# working.net
KiCad netlist of a schematic drawn in EAGLE
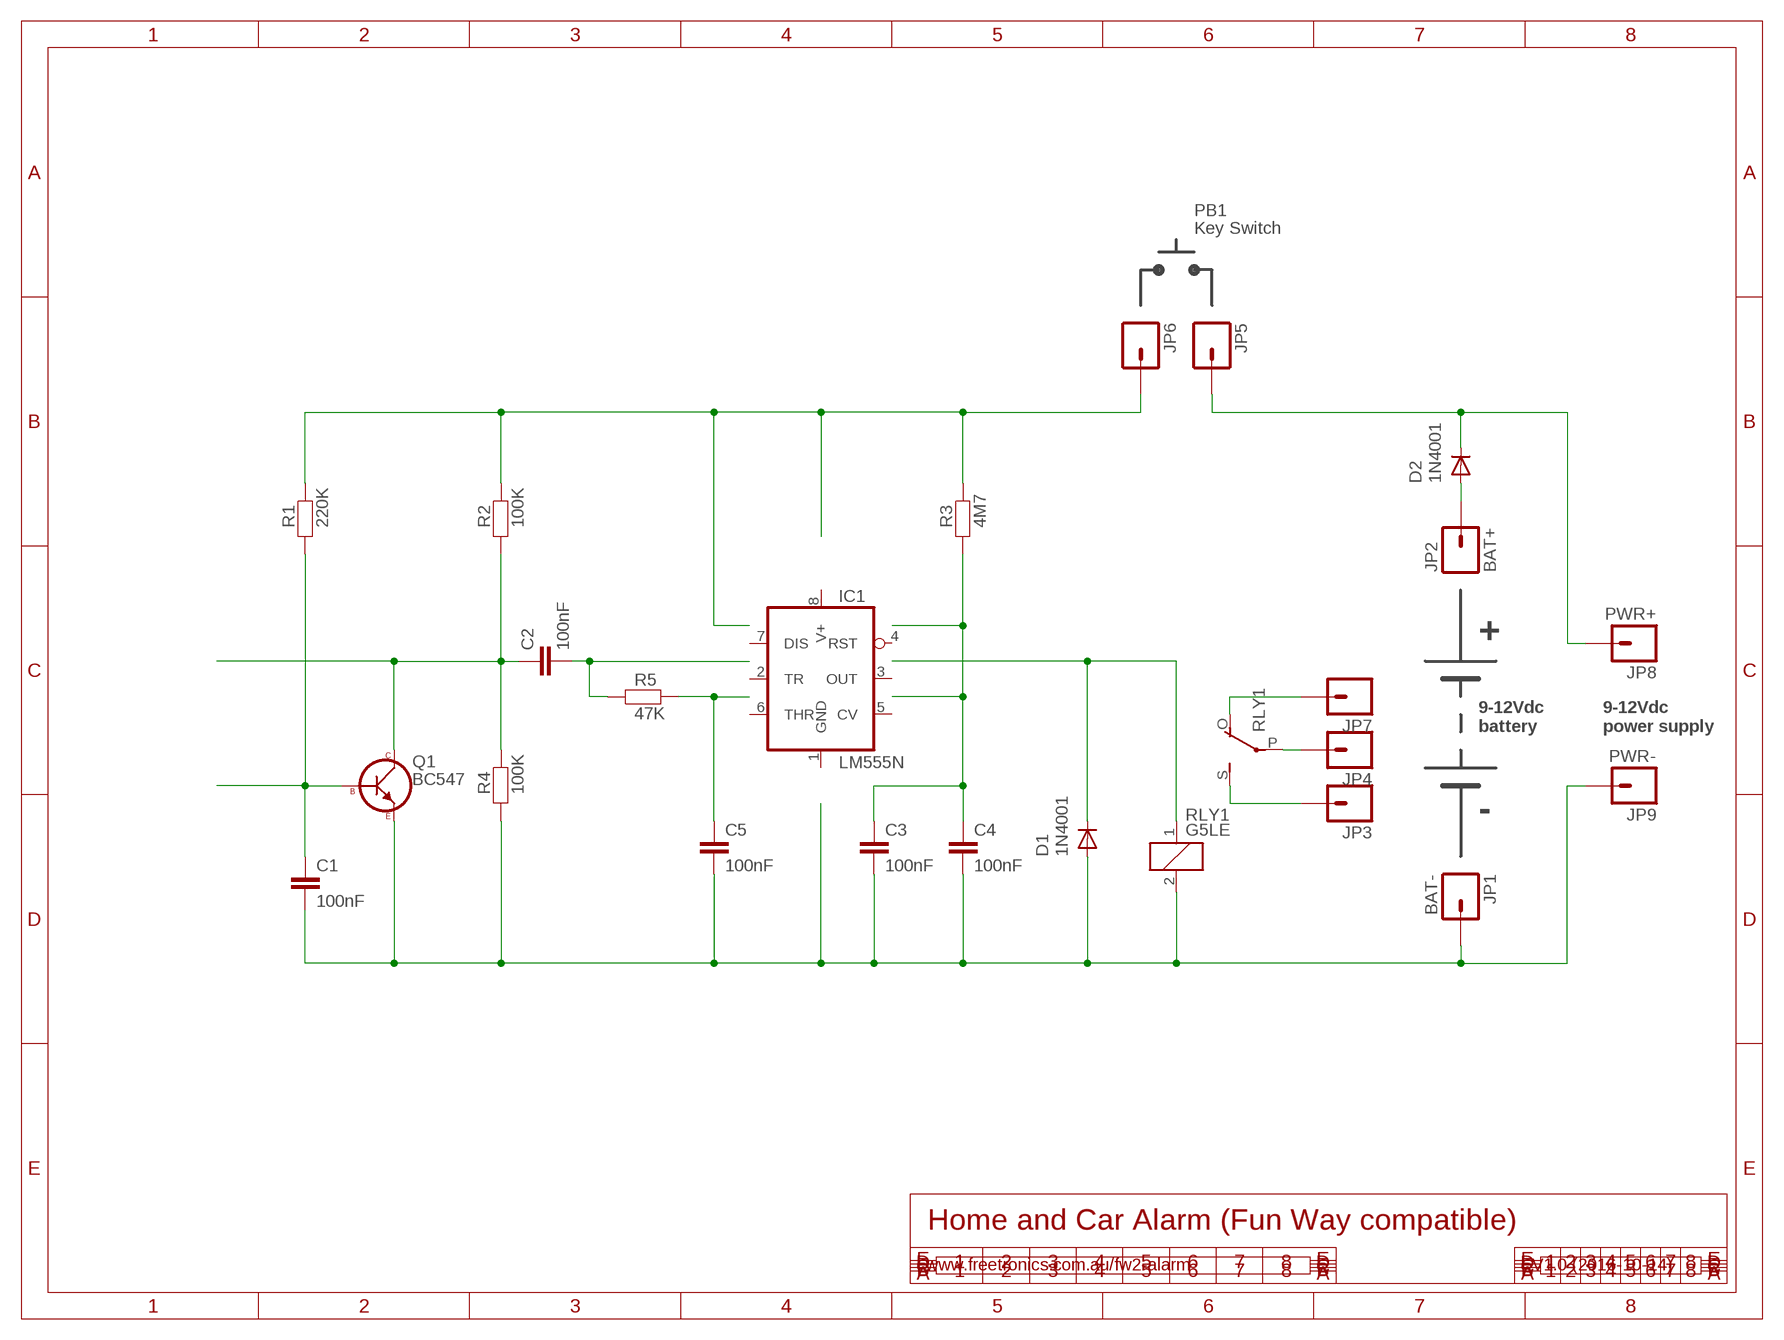
[diagram p0: schematic, sheet 1]

(export (version "E")
  (design (tool "Eeschema 10.0.6"))
  (components
    (comp (ref "C1")
      (value "100nF")
      (footprint "eagle-import:CAP-PTH-SMALL")
      (libsource (lib "eagle-import") (part "CAPPTH"))
    )
    (comp (ref "C2")
      (value "100nF")
      (footprint "eagle-import:CAP-PTH-SMALL")
      (libsource (lib "eagle-import") (part "CAPPTH"))
    )
    (comp (ref "C3")
      (value "100nF")
      (footprint "eagle-import:CAP-PTH-SMALL")
      (libsource (lib "eagle-import") (part "CAPPTH"))
    )
    (comp (ref "C4")
      (value "100nF")
      (footprint "eagle-import:CAP-PTH-SMALL")
      (libsource (lib "eagle-import") (part "CAPPTH"))
    )
    (comp (ref "C5")
      (value "100nF")
      (footprint "eagle-import:CAP-PTH-SMALL")
      (libsource (lib "eagle-import") (part "CAPPTH"))
    )
    (comp (ref "D1")
      (value "1N4001")
      (footprint "eagle-import:DIODE-1N4001")
      (libsource (lib "eagle-import") (part "DIODEPTH"))
    )
    (comp (ref "D2")
      (value "1N4001")
      (footprint "eagle-import:DIODE-1N4001")
      (libsource (lib "eagle-import") (part "DIODEPTH"))
    )
    (comp (ref "IC1")
      (value "LM555N")
      (footprint "eagle-import:DIL08")
      (libsource (lib "eagle-import") (part "555NLM"))
    )
    (comp (ref "JP1")
      (value "BAT-")
      (footprint "eagle-import:1X01")
      (libsource (lib "eagle-import") (part "M01PTH"))
    )
    (comp (ref "JP2")
      (value "BAT+")
      (footprint "eagle-import:1X01")
      (libsource (lib "eagle-import") (part "M01PTH"))
    )
    (comp (ref "JP3")
      (value "SPKR+")
      (footprint "eagle-import:1X01")
      (libsource (lib "eagle-import") (part "M01PTH"))
    )
    (comp (ref "JP4")
      (value "SPKR-")
      (footprint "eagle-import:1X01")
      (libsource (lib "eagle-import") (part "M01PTH"))
    )
    (comp (ref "JP5")
      (value "PWR-")
      (footprint "eagle-import:1X01")
      (libsource (lib "eagle-import") (part "M01PTH"))
    )
    (comp (ref "JP6")
      (value "PWR-")
      (footprint "eagle-import:1X01")
      (libsource (lib "eagle-import") (part "M01PTH"))
    )
    (comp (ref "JP7")
      (value "SPKR-")
      (footprint "eagle-import:1X01")
      (libsource (lib "eagle-import") (part "M01PTH"))
    )
    (comp (ref "JP8")
      (value "PWR+")
      (footprint "eagle-import:1X01")
      (libsource (lib "eagle-import") (part "M01PTH"))
    )
    (comp (ref "JP9")
      (value "PWR-")
      (footprint "eagle-import:1X01")
      (libsource (lib "eagle-import") (part "M01PTH"))
    )
    (comp (ref "Q1")
      (value "BC547")
      (footprint "eagle-import:TO-92")
      (libsource (lib "eagle-import") (part "BC547"))
    )
    (comp (ref "R1")
      (value "220K")
      (footprint "eagle-import:FREETRONICS_AXIAL-0.4")
      (libsource (lib "eagle-import") (part "FREETRONICS_RESISTORPTH2"))
    )
    (comp (ref "R2")
      (value "100K")
      (footprint "eagle-import:FREETRONICS_AXIAL-0.4")
      (libsource (lib "eagle-import") (part "FREETRONICS_RESISTORPTH2"))
    )
    (comp (ref "R3")
      (value "4M7")
      (footprint "eagle-import:FREETRONICS_AXIAL-0.4")
      (libsource (lib "eagle-import") (part "FREETRONICS_RESISTORPTH2"))
    )
    (comp (ref "R4")
      (value "100K")
      (footprint "eagle-import:FREETRONICS_AXIAL-0.4")
      (libsource (lib "eagle-import") (part "FREETRONICS_RESISTORPTH2"))
    )
    (comp (ref "R5")
      (value "47K")
      (footprint "eagle-import:FREETRONICS_AXIAL-0.4")
      (libsource (lib "eagle-import") (part "FREETRONICS_RESISTORPTH2"))
    )
    (comp (ref "RLY1")
      (value "G5LE")
      (footprint "eagle-import:G5LE")
      (libsource (lib "eagle-import") (part "G5LE"))
    )
  )
  (nets
    (net (code "1") (name "/GND") (class "Default")
      (node (ref "IC1") (pin "1") (pinfunction "GND_1") (pintype "power_in"))
    )
    (net (code "2") (name "/V+") (class "Default")
      (node (ref "IC1") (pin "8") (pinfunction "V+_8") (pintype "power_in"))
    )
    (net (code "3") (name "Net-(D1-PadC)") (class "Default")
      (node (ref "D1") (pin "C") (pinfunction "C_C") (pintype "passive"))
      (node (ref "RLY1") (pin "1") (pinfunction "1_1") (pintype "passive"))
    )
    (net (code "4") (name "Net-(D2-PadA)") (class "Default")
      (node (ref "D2") (pin "A") (pinfunction "A_A") (pintype "passive"))
      (node (ref "JP2") (pin "1") (pinfunction "1_1") (pintype "passive"))
    )
    (net (code "5") (name "Net-(D2-PadC)") (class "Default")
      (node (ref "D2") (pin "C") (pinfunction "C_C") (pintype "passive"))
      (node (ref "JP5") (pin "1") (pinfunction "1_1") (pintype "passive"))
      (node (ref "JP8") (pin "1") (pinfunction "1_1") (pintype "passive"))
    )
    (net (code "6") (name "Net-(JP3-Pad1)") (class "Default")
      (node (ref "JP3") (pin "1") (pinfunction "1_1") (pintype "passive"))
      (node (ref "RLY1") (pin "S") (pinfunction "S_S") (pintype "passive"))
    )
    (net (code "7") (name "Net-(JP4-Pad1)") (class "Default")
      (node (ref "JP4") (pin "1") (pinfunction "1_1") (pintype "passive"))
      (node (ref "RLY1") (pin "P") (pinfunction "P_P") (pintype "passive"))
    )
    (net (code "8") (name "Net-(JP7-Pad1)") (class "Default")
      (node (ref "JP7") (pin "1") (pinfunction "1_1") (pintype "passive"))
      (node (ref "RLY1") (pin "O") (pinfunction "O_O") (pintype "passive"))
    )
    (net (code "9") (name "Net-(Q1-B)") (class "Default")
      (node (ref "C1") (pin "1") (pinfunction "1_1") (pintype "passive"))
      (node (ref "Q1") (pin "2") (pinfunction "B_2") (pintype "passive"))
      (node (ref "R1") (pin "P$1") (pinfunction "1_P$1") (pintype "passive"))
    )
    (net (code "10") (name "Net-(Q1-C)") (class "Default")
      (node (ref "C2") (pin "1") (pinfunction "1_1") (pintype "passive"))
      (node (ref "Q1") (pin "1") (pinfunction "C_1") (pintype "passive"))
      (node (ref "R2") (pin "P$1") (pinfunction "1_P$1") (pintype "passive"))
      (node (ref "R4") (pin "P$2") (pinfunction "2_P$2") (pintype "passive"))
    )
    (net (code "11") (name "Net-(Q1-E)") (class "Default")
      (node (ref "C1") (pin "2") (pinfunction "2_2") (pintype "passive"))
      (node (ref "C3") (pin "2") (pinfunction "2_2") (pintype "passive"))
      (node (ref "C4") (pin "2") (pinfunction "2_2") (pintype "passive"))
      (node (ref "C5") (pin "2") (pinfunction "2_2") (pintype "passive"))
      (node (ref "D1") (pin "A") (pinfunction "A_A") (pintype "passive"))
      (node (ref "JP1") (pin "1") (pinfunction "1_1") (pintype "passive"))
      (node (ref "JP9") (pin "1") (pinfunction "1_1") (pintype "passive"))
      (node (ref "Q1") (pin "3") (pinfunction "E_3") (pintype "passive"))
      (node (ref "R4") (pin "P$1") (pinfunction "1_P$1") (pintype "passive"))
      (node (ref "RLY1") (pin "2") (pinfunction "2_2") (pintype "passive"))
    )
    (net (code "12") (name "Net-(R1-2)") (class "Default")
      (node (ref "JP6") (pin "1") (pinfunction "1_1") (pintype "passive"))
      (node (ref "R1") (pin "P$2") (pinfunction "2_P$2") (pintype "passive"))
      (node (ref "R2") (pin "P$2") (pinfunction "2_P$2") (pintype "passive"))
      (node (ref "R3") (pin "P$2") (pinfunction "2_P$2") (pintype "passive"))
    )
    (net (code "13") (name "Net-(R3-1)") (class "Default")
      (node (ref "C3") (pin "1") (pinfunction "1_1") (pintype "passive"))
      (node (ref "C4") (pin "1") (pinfunction "1_1") (pintype "passive"))
      (node (ref "R3") (pin "P$1") (pinfunction "1_P$1") (pintype "passive"))
    )
    (net (code "14") (name "Net-(R5-1)") (class "Default")
      (node (ref "C2") (pin "2") (pinfunction "2_2") (pintype "passive"))
      (node (ref "R5") (pin "P$1") (pinfunction "1_P$1") (pintype "passive"))
    )
    (net (code "15") (name "Net-(R5-2)") (class "Default")
      (node (ref "C5") (pin "1") (pinfunction "1_1") (pintype "passive"))
      (node (ref "R5") (pin "P$2") (pinfunction "2_P$2") (pintype "passive"))
    )
    (net (code "16") (name "unconnected-(IC1-CV-Pad5)") (class "Default")
      (node (ref "IC1") (pin "5") (pinfunction "CV_5") (pintype "input"))
    )
    (net (code "17") (name "unconnected-(IC1-DIS-Pad7)") (class "Default")
      (node (ref "IC1") (pin "7") (pinfunction "DIS_7") (pintype "input"))
    )
    (net (code "18") (name "unconnected-(IC1-OUT-Pad3)") (class "Default")
      (node (ref "IC1") (pin "3") (pinfunction "OUT_3") (pintype "output"))
    )
    (net (code "19") (name "unconnected-(IC1-RST-Pad4)") (class "Default")
      (node (ref "IC1") (pin "4") (pinfunction "RST_4") (pintype "input"))
    )
    (net (code "20") (name "unconnected-(IC1-THR-Pad6)") (class "Default")
      (node (ref "IC1") (pin "6") (pinfunction "THR_6") (pintype "input"))
    )
    (net (code "21") (name "unconnected-(IC1-TR-Pad2)") (class "Default")
      (node (ref "IC1") (pin "2") (pinfunction "TR_2") (pintype "input"))
    )
  )
)
